# Untitled_-_halv-xs-V3_4.net
KiCad netlist of a schematic drawn in EAGLE
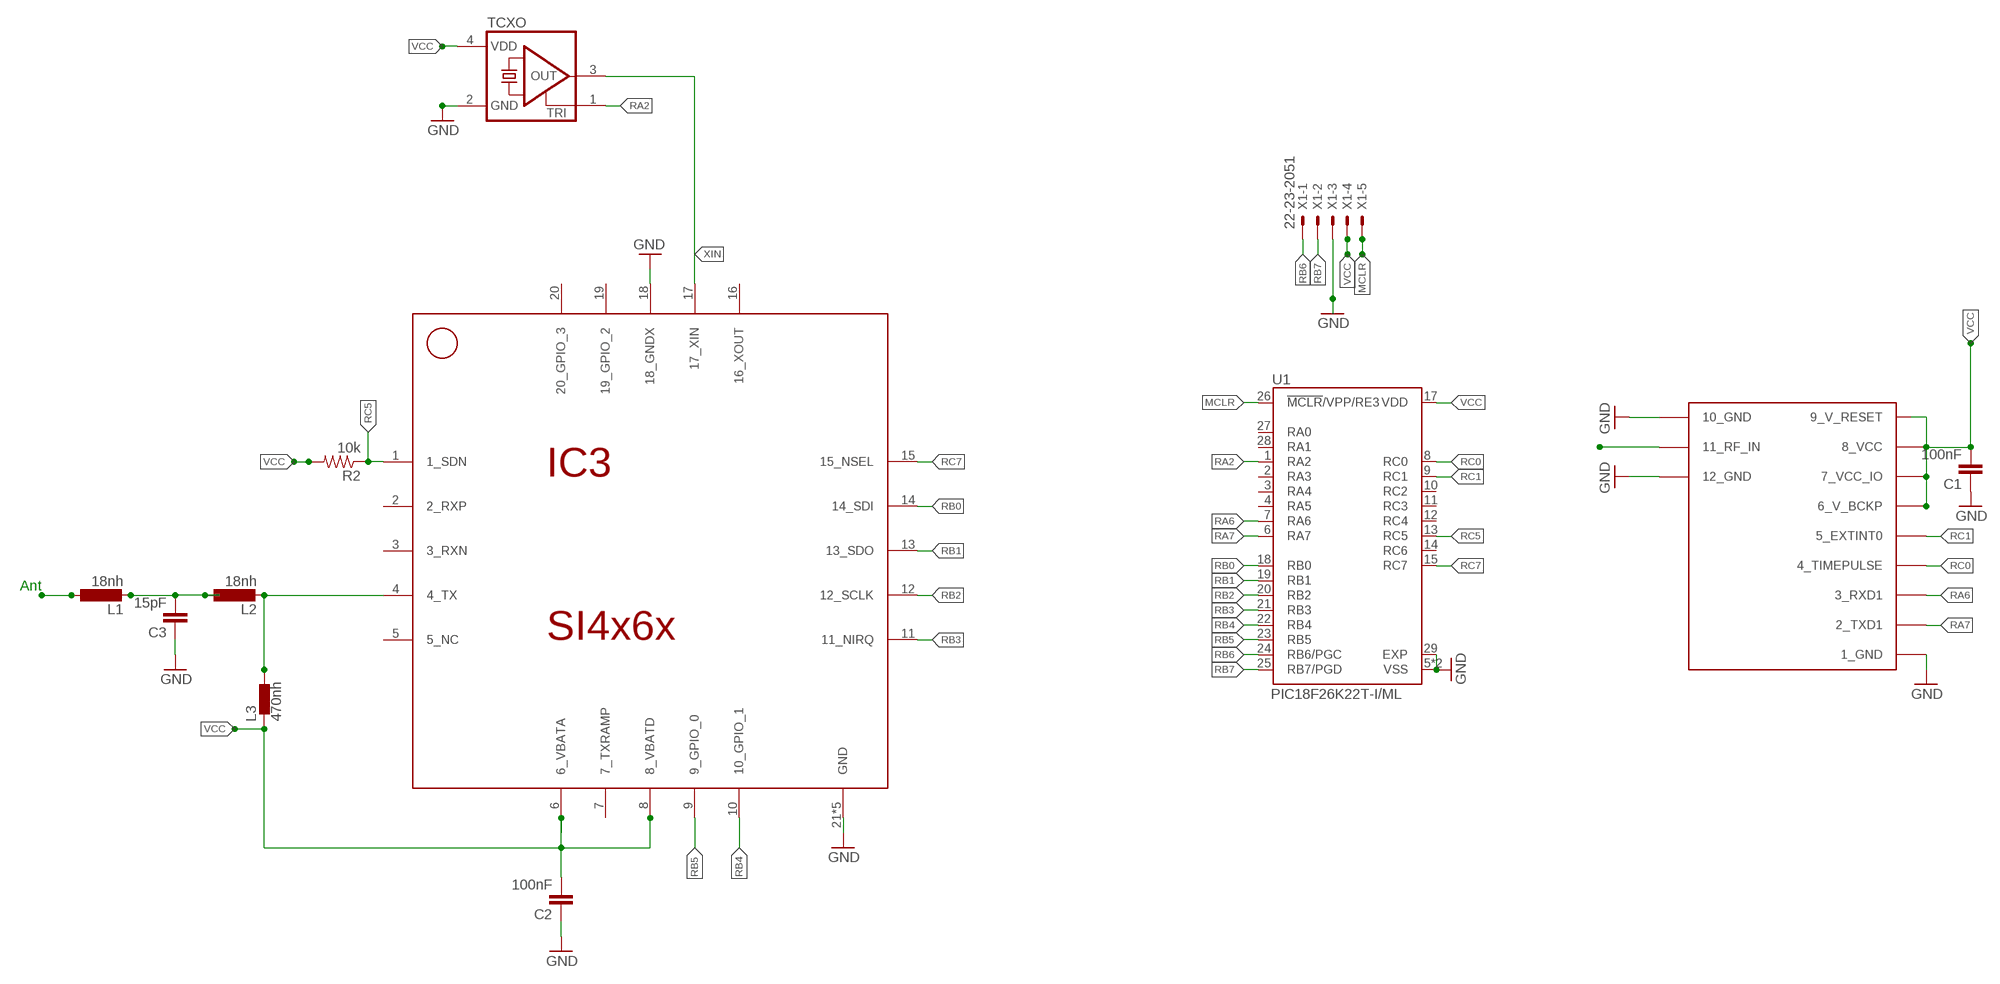
[diagram p0: schematic, sheet 1]

(export (version "E")
  (design (tool "Eeschema 10.0.6"))
  (components
    (comp (ref "C1")
      (value "100nF")
      (footprint "eagle-import:C0402")
      (libsource (lib "eagle-import") (part "C-EUC0402"))
    )
    (comp (ref "C2")
      (value "100nF")
      (footprint "eagle-import:C0402")
      (libsource (lib "eagle-import") (part "C-EUC0402"))
    )
    (comp (ref "C3")
      (value "15pF")
      (footprint "eagle-import:C0402")
      (libsource (lib "eagle-import") (part "C-EUC0402"))
    )
    (comp (ref "IC3")
      (value "SI4x6x")
      (footprint "eagle-import:QFN-20")
      (libsource (lib "eagle-import") (part "SI4463/4"))
    )
    (comp (ref "L1")
      (value "18nh")
      (footprint "eagle-import:L2012C")
      (libsource (lib "eagle-import") (part "L-EUL2012C"))
    )
    (comp (ref "L2")
      (value "18nh")
      (footprint "eagle-import:L2012C")
      (libsource (lib "eagle-import") (part "L-EUL2012C"))
    )
    (comp (ref "L3")
      (value "470nh")
      (footprint "eagle-import:0402")
      (libsource (lib "eagle-import") (part "BLM15HD601SN1"))
    )
    (comp (ref "R2")
      (value "10k")
      (footprint "eagle-import:R0402")
      (libsource (lib "eagle-import") (part "R-US_R0402"))
    )
    (comp (ref "TCXO")
      (value "CRYSTAL_3.2X2.5-TCXO")
      (footprint "eagle-import:CRYSTAL_3.2X2.5-TCXO")
      (libsource (lib "eagle-import") (part "CRYSTAL_3.2X2.5-TCXO"))
    )
    (comp (ref "U$1")
      (value "UBLOX_MAX")
      (footprint "eagle-import:UBLOX_MAX")
      (libsource (lib "eagle-import") (part "UBLOX_MAX"))
    )
    (comp (ref "U1")
      (value "PIC18F26K22T-I/ML")
      (footprint "eagle-import:QFN65P600X600X100-29N")
      (fields (field (name "MF") "Microchip"))
      (libsource (lib "eagle-import") (part "PIC18F26K22T-I/ML"))
    )
    (comp (ref "X1")
      (value "22-23-2051")
      (footprint "eagle-import:22-23-2051")
      (fields (field (name "MF") "MOLEX"))
      (libsource (lib "eagle-import") (part "22-23-2051"))
    )
  )
  (nets
    (net (code "1") (name "GND") (class "Default")
      (node (ref "C1") (pin "1") (pinfunction "1_1") (pintype "passive"))
      (node (ref "C2") (pin "1") (pinfunction "1_1") (pintype "passive"))
      (node (ref "C3") (pin "1") (pinfunction "1_1") (pintype "passive"))
      (node (ref "IC3") (pin "18") (pinfunction "18_GNDX_18") (pintype "bidirectional"))
      (node (ref "IC3") (pin "21") (pinfunction "GND_21") (pintype "bidirectional"))
      (node (ref "IC3") (pin "22") (pinfunction "GND_22") (pintype "bidirectional"))
      (node (ref "IC3") (pin "23") (pinfunction "GND_23") (pintype "bidirectional"))
      (node (ref "IC3") (pin "24") (pinfunction "GND_24") (pintype "bidirectional"))
      (node (ref "IC3") (pin "25") (pinfunction "GND_25") (pintype "bidirectional"))
      (node (ref "TCXO") (pin "2") (pinfunction "GND_2") (pintype "power_in"))
      (node (ref "U$1") (pin "10_GND") (pinfunction "10_GND_10_GND") (pintype "power_in"))
      (node (ref "U$1") (pin "12_GND") (pinfunction "12_GND_12_GND") (pintype "power_in"))
      (node (ref "U$1") (pin "1_GND") (pinfunction "1_GND_1_GND") (pintype "power_in"))
      (node (ref "U1") (pin "16") (pinfunction "VSS_16") (pintype "power_in"))
      (node (ref "U1") (pin "29") (pinfunction "EXP_29") (pintype "power_in"))
      (node (ref "U1") (pin "5") (pinfunction "VSS_5") (pintype "power_in"))
      (node (ref "X1") (pin "3") (pinfunction "S_3") (pintype "passive"))
    )
    (net (code "2") (name "MCLR") (class "Default")
      (node (ref "U1") (pin "26") (pinfunction "~{MCLR}/VPP/RE3_26") (pintype "input"))
      (node (ref "X1") (pin "5") (pinfunction "S_5") (pintype "passive"))
    )
    (net (code "3") (name "Net-(C3-Pad2)") (class "Default")
      (node (ref "C3") (pin "2") (pinfunction "2_2") (pintype "passive"))
      (node (ref "L1") (pin "2") (pinfunction "2_2") (pintype "passive"))
      (node (ref "L2") (pin "1") (pinfunction "1_1") (pintype "passive"))
    )
    (net (code "4") (name "Net-(IC3-4_TX)") (class "Default")
      (node (ref "IC3") (pin "4") (pinfunction "4_TX_4") (pintype "bidirectional"))
      (node (ref "L2") (pin "2") (pinfunction "2_2") (pintype "passive"))
      (node (ref "L3") (pin "2") (pinfunction "2_2") (pintype "passive"))
    )
    (net (code "5") (name "RA2") (class "Default")
      (node (ref "TCXO") (pin "1") (pinfunction "TRI_1") (pintype "input"))
      (node (ref "U1") (pin "1") (pinfunction "RA2_1") (pintype "bidirectional"))
    )
    (net (code "6") (name "RA6") (class "Default")
      (node (ref "U$1") (pin "3_RXD1") (pinfunction "3_RXD1_3_RXD1") (pintype "bidirectional"))
      (node (ref "U1") (pin "7") (pinfunction "RA6_7") (pintype "bidirectional"))
    )
    (net (code "7") (name "RA7") (class "Default")
      (node (ref "U$1") (pin "2_TXD1") (pinfunction "2_TXD1_2_TXD1") (pintype "bidirectional"))
      (node (ref "U1") (pin "6") (pinfunction "RA7_6") (pintype "bidirectional"))
    )
    (net (code "8") (name "RB0") (class "Default")
      (node (ref "IC3") (pin "14") (pinfunction "14_SDI_14") (pintype "bidirectional"))
      (node (ref "U1") (pin "18") (pinfunction "RB0_18") (pintype "bidirectional"))
    )
    (net (code "9") (name "RB1") (class "Default")
      (node (ref "IC3") (pin "13") (pinfunction "13_SDO_13") (pintype "bidirectional"))
      (node (ref "U1") (pin "19") (pinfunction "RB1_19") (pintype "bidirectional"))
    )
    (net (code "10") (name "RB2") (class "Default")
      (node (ref "IC3") (pin "12") (pinfunction "12_SCLK_12") (pintype "bidirectional"))
      (node (ref "U1") (pin "20") (pinfunction "RB2_20") (pintype "bidirectional"))
    )
    (net (code "11") (name "RB3") (class "Default")
      (node (ref "IC3") (pin "11") (pinfunction "11_NIRQ_11") (pintype "bidirectional"))
      (node (ref "U1") (pin "21") (pinfunction "RB3_21") (pintype "bidirectional"))
    )
    (net (code "12") (name "RB4") (class "Default")
      (node (ref "IC3") (pin "10") (pinfunction "10_GPIO_1_10") (pintype "bidirectional"))
      (node (ref "U1") (pin "22") (pinfunction "RB4_22") (pintype "bidirectional"))
    )
    (net (code "13") (name "RB5") (class "Default")
      (node (ref "IC3") (pin "9") (pinfunction "9_GPIO_0_9") (pintype "bidirectional"))
      (node (ref "U1") (pin "23") (pinfunction "RB5_23") (pintype "bidirectional"))
    )
    (net (code "14") (name "RB6") (class "Default")
      (node (ref "U1") (pin "24") (pinfunction "RB6/PGC_24") (pintype "bidirectional"))
      (node (ref "X1") (pin "1") (pinfunction "S_1") (pintype "passive"))
    )
    (net (code "15") (name "RB7") (class "Default")
      (node (ref "U1") (pin "25") (pinfunction "RB7/PGD_25") (pintype "bidirectional"))
      (node (ref "X1") (pin "2") (pinfunction "S_2") (pintype "passive"))
    )
    (net (code "16") (name "RC0") (class "Default")
      (node (ref "U$1") (pin "4_TIMEPULSE") (pinfunction "4_TIMEPULSE_4_TIMEPULSE") (pintype "bidirectional"))
      (node (ref "U1") (pin "8") (pinfunction "RC0_8") (pintype "bidirectional"))
    )
    (net (code "17") (name "RC1") (class "Default")
      (node (ref "U$1") (pin "5_EXTINT0") (pinfunction "5_EXTINT0_5_EXTINT0") (pintype "bidirectional"))
      (node (ref "U1") (pin "9") (pinfunction "RC1_9") (pintype "bidirectional"))
    )
    (net (code "18") (name "RC5") (class "Default")
      (node (ref "IC3") (pin "1") (pinfunction "1_SDN_1") (pintype "bidirectional"))
      (node (ref "R2") (pin "1") (pinfunction "1_1") (pintype "passive"))
      (node (ref "U1") (pin "13") (pinfunction "RC5_13") (pintype "bidirectional"))
    )
    (net (code "19") (name "RC7") (class "Default")
      (node (ref "IC3") (pin "15") (pinfunction "15_NSEL_15") (pintype "bidirectional"))
      (node (ref "U1") (pin "15") (pinfunction "RC7_15") (pintype "bidirectional"))
    )
    (net (code "20") (name "VCC") (class "Default")
      (node (ref "C1") (pin "2") (pinfunction "2_2") (pintype "passive"))
      (node (ref "C2") (pin "2") (pinfunction "2_2") (pintype "passive"))
      (node (ref "IC3") (pin "6") (pinfunction "6_VBATA_6") (pintype "bidirectional"))
      (node (ref "IC3") (pin "8") (pinfunction "8_VBATD_8") (pintype "bidirectional"))
      (node (ref "L3") (pin "1") (pinfunction "1_1") (pintype "passive"))
      (node (ref "R2") (pin "2") (pinfunction "2_2") (pintype "passive"))
      (node (ref "TCXO") (pin "4") (pinfunction "VDD_4") (pintype "power_in"))
      (node (ref "U$1") (pin "6_V_BCKP") (pinfunction "6_V_BCKP_6_V_BCKP") (pintype "bidirectional"))
      (node (ref "U$1") (pin "7_VCC_IO") (pinfunction "7_VCC_IO_7_VCC_IO") (pintype "power_in"))
      (node (ref "U$1") (pin "8_VCC") (pinfunction "8_VCC_8_VCC") (pintype "power_in"))
      (node (ref "U$1") (pin "9_V_RESET") (pinfunction "9_V_RESET_9_V_RESET") (pintype "power_in"))
      (node (ref "U1") (pin "17") (pinfunction "VDD_17") (pintype "power_in"))
      (node (ref "X1") (pin "4") (pinfunction "S_4") (pintype "passive"))
    )
    (net (code "21") (name "XIN") (class "Default")
      (node (ref "IC3") (pin "17") (pinfunction "17_XIN_17") (pintype "bidirectional"))
      (node (ref "TCXO") (pin "3") (pinfunction "OUT_3") (pintype "output"))
    )
    (net (code "22") (name "unconnected-(IC3-2_RXP-Pad2)") (class "Default")
      (node (ref "IC3") (pin "2") (pinfunction "2_RXP_2") (pintype "bidirectional"))
    )
    (net (code "23") (name "unconnected-(IC3-3_RXN-Pad3)") (class "Default")
      (node (ref "IC3") (pin "3") (pinfunction "3_RXN_3") (pintype "bidirectional"))
    )
    (net (code "24") (name "unconnected-(IC3-5_NC-Pad5)") (class "Default")
      (node (ref "IC3") (pin "5") (pinfunction "5_NC_5") (pintype "bidirectional"))
    )
    (net (code "25") (name "unconnected-(IC3-7_TXRAMP-Pad7)") (class "Default")
      (node (ref "IC3") (pin "7") (pinfunction "7_TXRAMP_7") (pintype "bidirectional"))
    )
    (net (code "26") (name "unconnected-(IC3-16_XOUT-Pad16)") (class "Default")
      (node (ref "IC3") (pin "16") (pinfunction "16_XOUT_16") (pintype "bidirectional"))
    )
    (net (code "27") (name "unconnected-(IC3-19_GPIO_2-Pad19)") (class "Default")
      (node (ref "IC3") (pin "19") (pinfunction "19_GPIO_2_19") (pintype "bidirectional"))
    )
    (net (code "28") (name "unconnected-(IC3-20_GPIO_3-Pad20)") (class "Default")
      (node (ref "IC3") (pin "20") (pinfunction "20_GPIO_3_20") (pintype "bidirectional"))
    )
    (net (code "29") (name "unconnected-(L1-Pad1)") (class "Default")
      (node (ref "L1") (pin "1") (pinfunction "1_1") (pintype "passive"))
    )
    (net (code "30") (name "unconnected-(U$1-Pad11_RF_IN)") (class "Default")
      (node (ref "U$1") (pin "11_RF_IN") (pinfunction "11_RF_IN_11_RF_IN") (pintype "bidirectional"))
    )
    (net (code "31") (name "unconnected-(U1-RA0-Pad27)") (class "Default")
      (node (ref "U1") (pin "27") (pinfunction "RA0_27") (pintype "bidirectional"))
    )
    (net (code "32") (name "unconnected-(U1-RA1-Pad28)") (class "Default")
      (node (ref "U1") (pin "28") (pinfunction "RA1_28") (pintype "bidirectional"))
    )
    (net (code "33") (name "unconnected-(U1-RA3-Pad2)") (class "Default")
      (node (ref "U1") (pin "2") (pinfunction "RA3_2") (pintype "bidirectional"))
    )
    (net (code "34") (name "unconnected-(U1-RA4-Pad3)") (class "Default")
      (node (ref "U1") (pin "3") (pinfunction "RA4_3") (pintype "bidirectional"))
    )
    (net (code "35") (name "unconnected-(U1-RA5-Pad4)") (class "Default")
      (node (ref "U1") (pin "4") (pinfunction "RA5_4") (pintype "bidirectional"))
    )
    (net (code "36") (name "unconnected-(U1-RC2-Pad10)") (class "Default")
      (node (ref "U1") (pin "10") (pinfunction "RC2_10") (pintype "bidirectional"))
    )
    (net (code "37") (name "unconnected-(U1-RC3-Pad11)") (class "Default")
      (node (ref "U1") (pin "11") (pinfunction "RC3_11") (pintype "bidirectional"))
    )
    (net (code "38") (name "unconnected-(U1-RC4-Pad12)") (class "Default")
      (node (ref "U1") (pin "12") (pinfunction "RC4_12") (pintype "bidirectional"))
    )
    (net (code "39") (name "unconnected-(U1-RC6-Pad14)") (class "Default")
      (node (ref "U1") (pin "14") (pinfunction "RC6_14") (pintype "bidirectional"))
    )
  )
)
